# BMS_Cell_Charging_Adapter_rev2.net
KiCad netlist of a schematic drawn in EAGLE
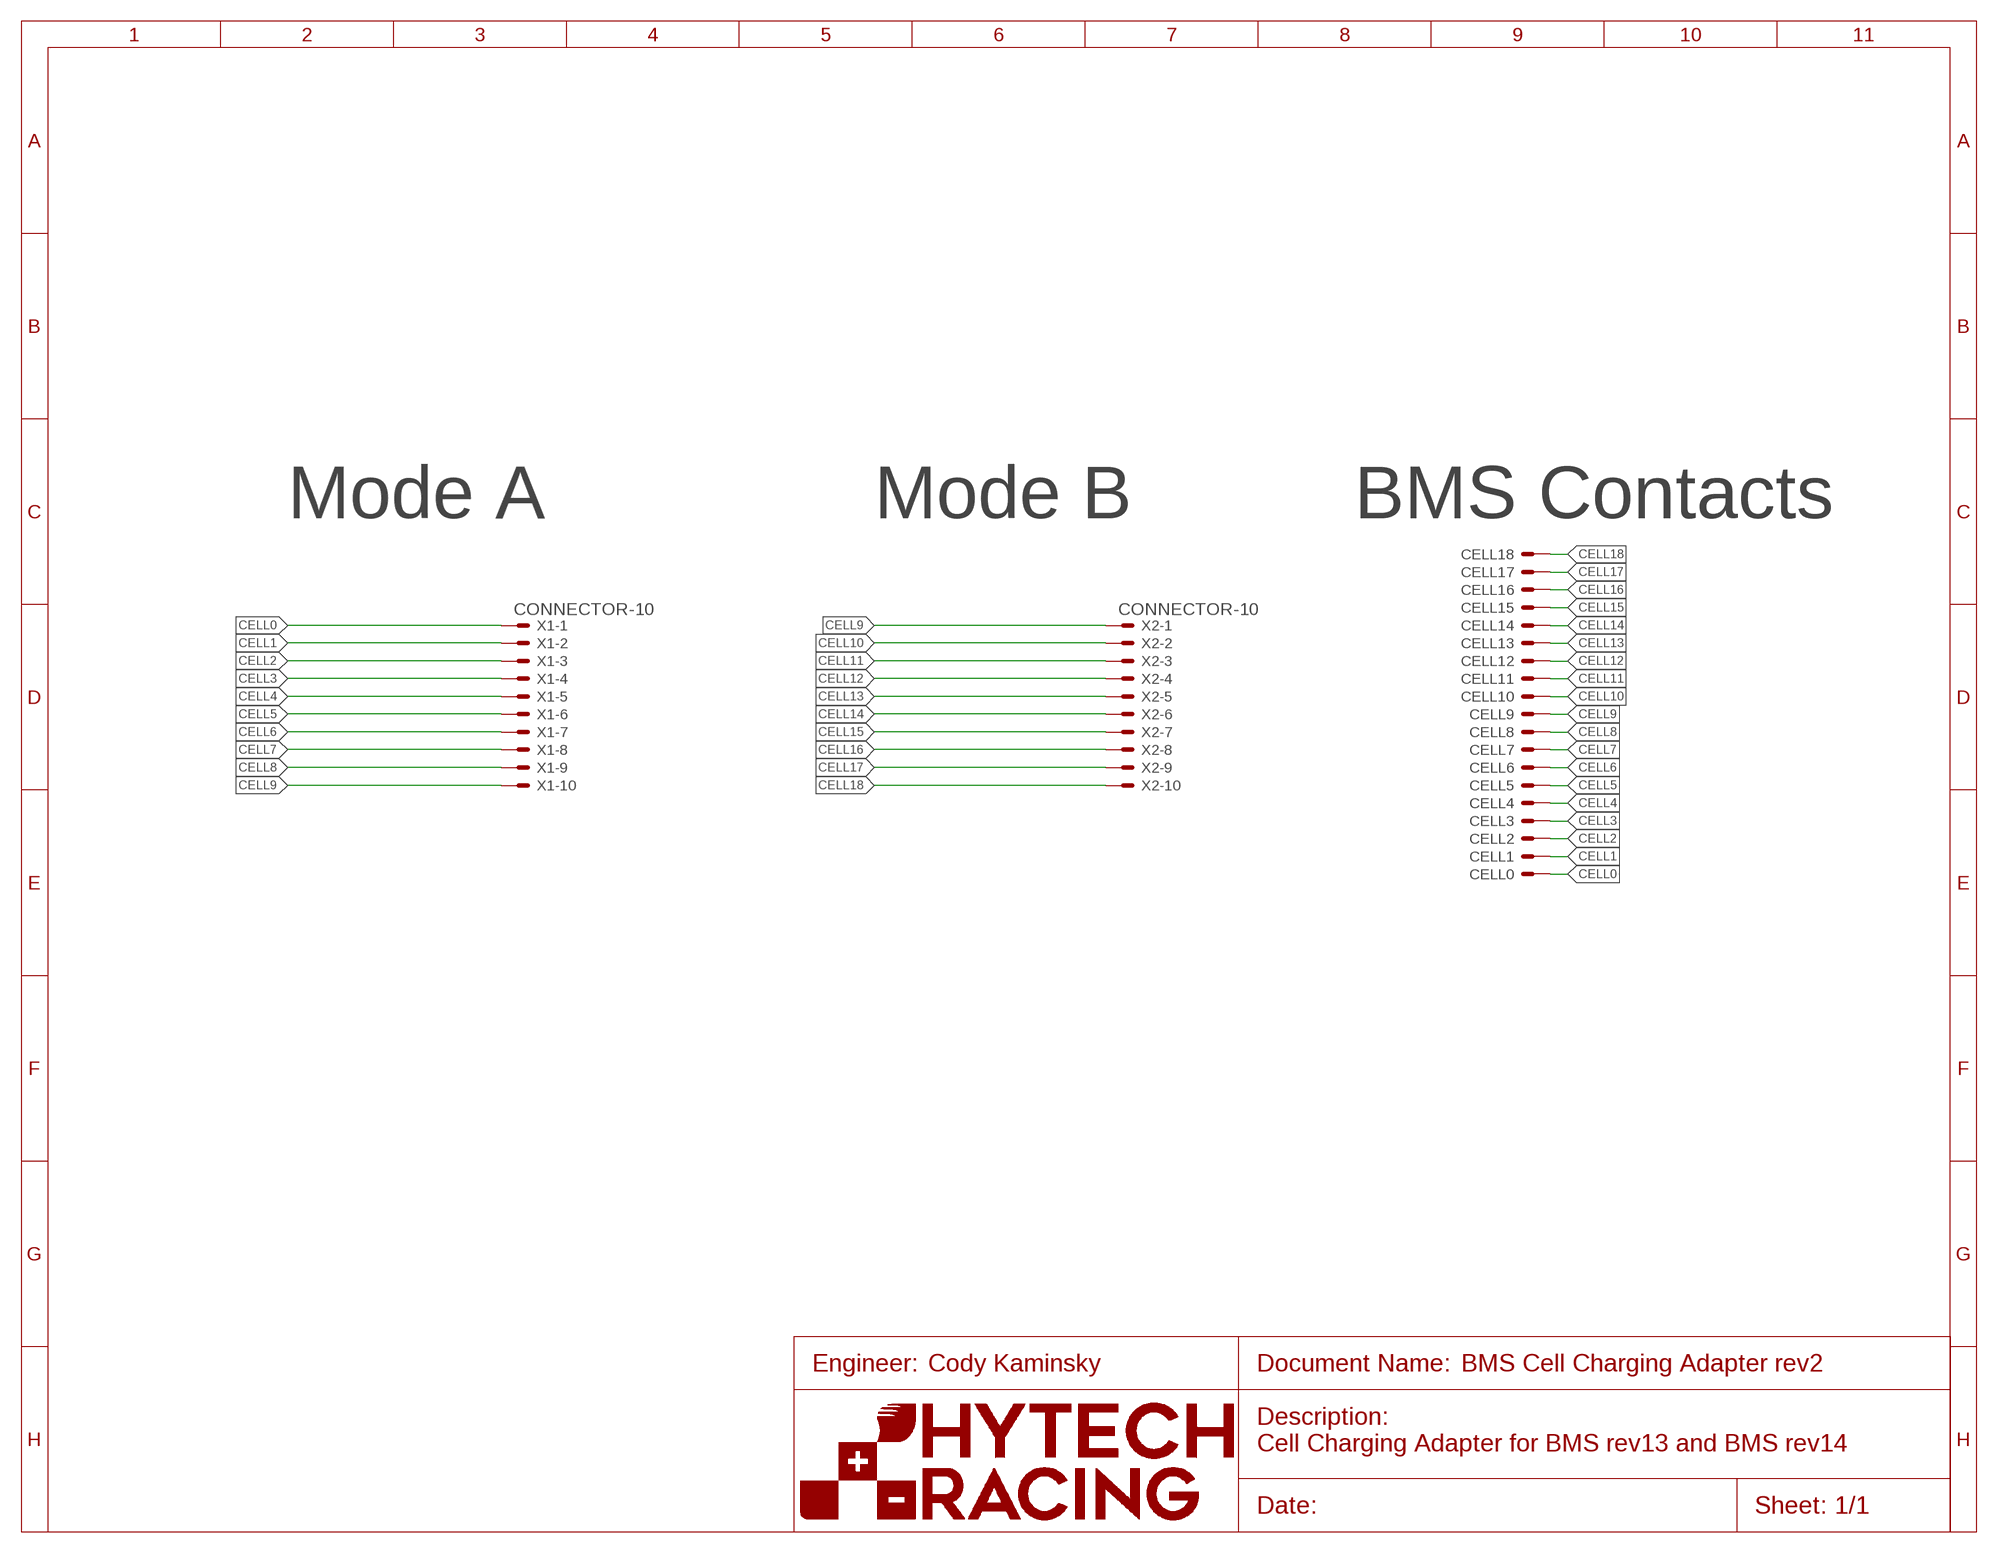
[diagram p0: schematic, sheet 1]

(export (version "E")
  (design (tool "Eeschema 10.0.6"))
  (components
    (comp (ref "CELL0")
      (value "BATTERY_SPRING_KEYSTONE5222")
      (footprint "eagle-import:KEYSTONE5222")
      (libsource (lib "eagle-import") (part "BATTERY_SPRING_KEYSTONE5222"))
    )
    (comp (ref "CELL1")
      (value "BATTERY_SPRING_KEYSTONE5222")
      (footprint "eagle-import:KEYSTONE5222")
      (libsource (lib "eagle-import") (part "BATTERY_SPRING_KEYSTONE5222"))
    )
    (comp (ref "CELL2")
      (value "BATTERY_SPRING_KEYSTONE5222")
      (footprint "eagle-import:KEYSTONE5222")
      (libsource (lib "eagle-import") (part "BATTERY_SPRING_KEYSTONE5222"))
    )
    (comp (ref "CELL3")
      (value "BATTERY_SPRING_KEYSTONE5222")
      (footprint "eagle-import:KEYSTONE5222")
      (libsource (lib "eagle-import") (part "BATTERY_SPRING_KEYSTONE5222"))
    )
    (comp (ref "CELL4")
      (value "BATTERY_SPRING_KEYSTONE5222")
      (footprint "eagle-import:KEYSTONE5222")
      (libsource (lib "eagle-import") (part "BATTERY_SPRING_KEYSTONE5222"))
    )
    (comp (ref "CELL5")
      (value "BATTERY_SPRING_KEYSTONE5222")
      (footprint "eagle-import:KEYSTONE5222")
      (libsource (lib "eagle-import") (part "BATTERY_SPRING_KEYSTONE5222"))
    )
    (comp (ref "CELL6")
      (value "BATTERY_SPRING_KEYSTONE5222")
      (footprint "eagle-import:KEYSTONE5222")
      (libsource (lib "eagle-import") (part "BATTERY_SPRING_KEYSTONE5222"))
    )
    (comp (ref "CELL7")
      (value "BATTERY_SPRING_KEYSTONE5222")
      (footprint "eagle-import:KEYSTONE5222")
      (libsource (lib "eagle-import") (part "BATTERY_SPRING_KEYSTONE5222"))
    )
    (comp (ref "CELL8")
      (value "BATTERY_SPRING_KEYSTONE5222")
      (footprint "eagle-import:KEYSTONE5222")
      (libsource (lib "eagle-import") (part "BATTERY_SPRING_KEYSTONE5222"))
    )
    (comp (ref "CELL9")
      (value "BATTERY_SPRING_KEYSTONE5222")
      (footprint "eagle-import:KEYSTONE5222")
      (libsource (lib "eagle-import") (part "BATTERY_SPRING_KEYSTONE5222"))
    )
    (comp (ref "CELL10")
      (value "BATTERY_SPRING_KEYSTONE5222")
      (footprint "eagle-import:KEYSTONE5222")
      (libsource (lib "eagle-import") (part "BATTERY_SPRING_KEYSTONE5222"))
    )
    (comp (ref "CELL11")
      (value "BATTERY_SPRING_KEYSTONE5222")
      (footprint "eagle-import:KEYSTONE5222")
      (libsource (lib "eagle-import") (part "BATTERY_SPRING_KEYSTONE5222"))
    )
    (comp (ref "CELL12")
      (value "BATTERY_SPRING_KEYSTONE5222")
      (footprint "eagle-import:KEYSTONE5222")
      (libsource (lib "eagle-import") (part "BATTERY_SPRING_KEYSTONE5222"))
    )
    (comp (ref "CELL13")
      (value "BATTERY_SPRING_KEYSTONE5222")
      (footprint "eagle-import:KEYSTONE5222")
      (libsource (lib "eagle-import") (part "BATTERY_SPRING_KEYSTONE5222"))
    )
    (comp (ref "CELL14")
      (value "BATTERY_SPRING_KEYSTONE5222")
      (footprint "eagle-import:KEYSTONE5222")
      (libsource (lib "eagle-import") (part "BATTERY_SPRING_KEYSTONE5222"))
    )
    (comp (ref "CELL15")
      (value "BATTERY_SPRING_KEYSTONE5222")
      (footprint "eagle-import:KEYSTONE5222")
      (libsource (lib "eagle-import") (part "BATTERY_SPRING_KEYSTONE5222"))
    )
    (comp (ref "CELL16")
      (value "BATTERY_SPRING_KEYSTONE5222")
      (footprint "eagle-import:KEYSTONE5222")
      (libsource (lib "eagle-import") (part "BATTERY_SPRING_KEYSTONE5222"))
    )
    (comp (ref "CELL17")
      (value "BATTERY_SPRING_KEYSTONE5222")
      (footprint "eagle-import:KEYSTONE5222")
      (libsource (lib "eagle-import") (part "BATTERY_SPRING_KEYSTONE5222"))
    )
    (comp (ref "CELL18")
      (value "BATTERY_SPRING_KEYSTONE5222")
      (footprint "eagle-import:KEYSTONE5222")
      (libsource (lib "eagle-import") (part "BATTERY_SPRING_KEYSTONE5222"))
    )
    (comp (ref "X1")
      (value "CONNECTOR-10")
      (footprint "eagle-import:MINIFIT_5566-10")
      (libsource (lib "eagle-import") (part "CONNECTOR-10"))
    )
    (comp (ref "X2")
      (value "CONNECTOR-10")
      (footprint "eagle-import:MINIFIT_5566-10")
      (libsource (lib "eagle-import") (part "CONNECTOR-10"))
    )
  )
  (nets
    (net (code "1") (name "CELL0") (class "Default")
      (node (ref "CELL0") (pin "P$1") (pinfunction "S_P$1") (pintype "passive"))
      (node (ref "X1") (pin "1") (pinfunction "S_1") (pintype "passive"))
    )
    (net (code "2") (name "CELL1") (class "Default")
      (node (ref "CELL1") (pin "P$1") (pinfunction "S_P$1") (pintype "passive"))
      (node (ref "X1") (pin "2") (pinfunction "S_2") (pintype "passive"))
    )
    (net (code "3") (name "CELL2") (class "Default")
      (node (ref "CELL2") (pin "P$1") (pinfunction "S_P$1") (pintype "passive"))
      (node (ref "X1") (pin "3") (pinfunction "S_3") (pintype "passive"))
    )
    (net (code "4") (name "CELL3") (class "Default")
      (node (ref "CELL3") (pin "P$1") (pinfunction "S_P$1") (pintype "passive"))
      (node (ref "X1") (pin "4") (pinfunction "S_4") (pintype "passive"))
    )
    (net (code "5") (name "CELL4") (class "Default")
      (node (ref "CELL4") (pin "P$1") (pinfunction "S_P$1") (pintype "passive"))
      (node (ref "X1") (pin "5") (pinfunction "S_5") (pintype "passive"))
    )
    (net (code "6") (name "CELL5") (class "Default")
      (node (ref "CELL5") (pin "P$1") (pinfunction "S_P$1") (pintype "passive"))
      (node (ref "X1") (pin "6") (pinfunction "S_6") (pintype "passive"))
    )
    (net (code "7") (name "CELL6") (class "Default")
      (node (ref "CELL6") (pin "P$1") (pinfunction "S_P$1") (pintype "passive"))
      (node (ref "X1") (pin "7") (pinfunction "S_7") (pintype "passive"))
    )
    (net (code "8") (name "CELL7") (class "Default")
      (node (ref "CELL7") (pin "P$1") (pinfunction "S_P$1") (pintype "passive"))
      (node (ref "X1") (pin "8") (pinfunction "S_8") (pintype "passive"))
    )
    (net (code "9") (name "CELL8") (class "Default")
      (node (ref "CELL8") (pin "P$1") (pinfunction "S_P$1") (pintype "passive"))
      (node (ref "X1") (pin "9") (pinfunction "S_9") (pintype "passive"))
    )
    (net (code "10") (name "CELL9") (class "Default")
      (node (ref "CELL9") (pin "P$1") (pinfunction "S_P$1") (pintype "passive"))
      (node (ref "X1") (pin "10") (pinfunction "S_10") (pintype "passive"))
      (node (ref "X2") (pin "1") (pinfunction "S_1") (pintype "passive"))
    )
    (net (code "11") (name "CELL10") (class "Default")
      (node (ref "CELL10") (pin "P$1") (pinfunction "S_P$1") (pintype "passive"))
      (node (ref "X2") (pin "2") (pinfunction "S_2") (pintype "passive"))
    )
    (net (code "12") (name "CELL11") (class "Default")
      (node (ref "CELL11") (pin "P$1") (pinfunction "S_P$1") (pintype "passive"))
      (node (ref "X2") (pin "3") (pinfunction "S_3") (pintype "passive"))
    )
    (net (code "13") (name "CELL12") (class "Default")
      (node (ref "CELL12") (pin "P$1") (pinfunction "S_P$1") (pintype "passive"))
      (node (ref "X2") (pin "4") (pinfunction "S_4") (pintype "passive"))
    )
    (net (code "14") (name "CELL13") (class "Default")
      (node (ref "CELL13") (pin "P$1") (pinfunction "S_P$1") (pintype "passive"))
      (node (ref "X2") (pin "5") (pinfunction "S_5") (pintype "passive"))
    )
    (net (code "15") (name "CELL14") (class "Default")
      (node (ref "CELL14") (pin "P$1") (pinfunction "S_P$1") (pintype "passive"))
      (node (ref "X2") (pin "6") (pinfunction "S_6") (pintype "passive"))
    )
    (net (code "16") (name "CELL15") (class "Default")
      (node (ref "CELL15") (pin "P$1") (pinfunction "S_P$1") (pintype "passive"))
      (node (ref "X2") (pin "7") (pinfunction "S_7") (pintype "passive"))
    )
    (net (code "17") (name "CELL16") (class "Default")
      (node (ref "CELL16") (pin "P$1") (pinfunction "S_P$1") (pintype "passive"))
      (node (ref "X2") (pin "8") (pinfunction "S_8") (pintype "passive"))
    )
    (net (code "18") (name "CELL17") (class "Default")
      (node (ref "CELL17") (pin "P$1") (pinfunction "S_P$1") (pintype "passive"))
      (node (ref "X2") (pin "9") (pinfunction "S_9") (pintype "passive"))
    )
    (net (code "19") (name "CELL18") (class "Default")
      (node (ref "CELL18") (pin "P$1") (pinfunction "S_P$1") (pintype "passive"))
      (node (ref "X2") (pin "10") (pinfunction "S_10") (pintype "passive"))
    )
  )
)
